# W070C.net
KiCad netlist of a schematic drawn in EAGLE
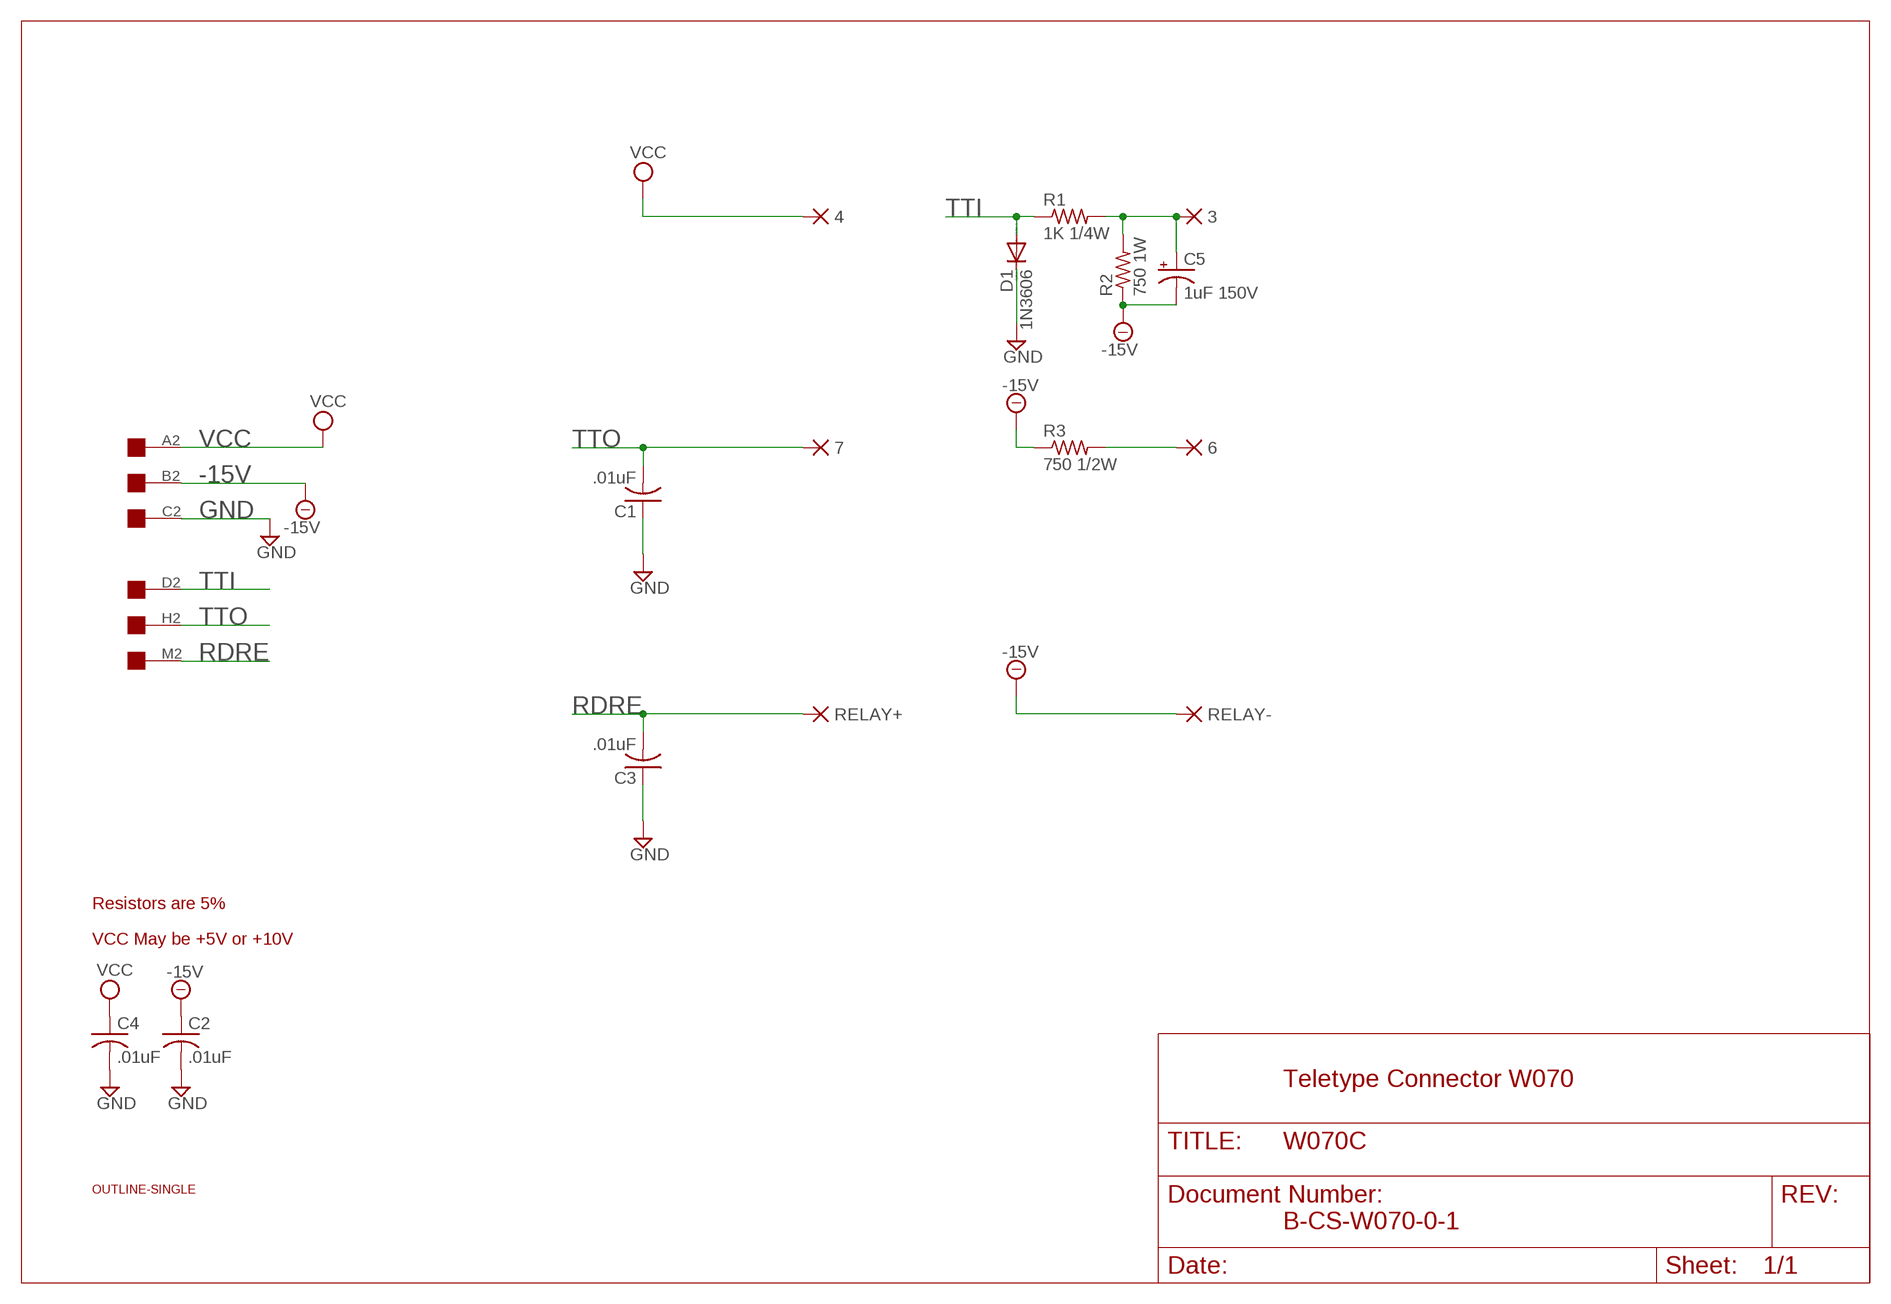
[diagram p0: schematic, sheet 1]

(export (version "E")
  (design (tool "Eeschema 10.0.6"))
  (components
    (comp (ref "3")
      (value "PAD-0465")
      (footprint "eagle-import:0465")
      (libsource (lib "eagle-import") (part "PAD-0465"))
    )
    (comp (ref "4")
      (value "PAD-0465")
      (footprint "eagle-import:0465")
      (libsource (lib "eagle-import") (part "PAD-0465"))
    )
    (comp (ref "6")
      (value "PAD-0465")
      (footprint "eagle-import:0465")
      (libsource (lib "eagle-import") (part "PAD-0465"))
    )
    (comp (ref "7")
      (value "PAD-0465")
      (footprint "eagle-import:0465")
      (libsource (lib "eagle-import") (part "PAD-0465"))
    )
    (comp (ref "C1")
      (value ".01uF")
      (footprint "eagle-import:C050-025X075")
      (libsource (lib "eagle-import") (part "C-US050-025X075"))
    )
    (comp (ref "C2")
      (value ".01uF")
      (footprint "eagle-import:C050-025X075")
      (libsource (lib "eagle-import") (part "C-US050-025X075"))
    )
    (comp (ref "C3")
      (value ".01uF")
      (footprint "eagle-import:C050-025X075")
      (libsource (lib "eagle-import") (part "C-US050-025X075"))
    )
    (comp (ref "C4")
      (value ".01uF")
      (footprint "eagle-import:C050-025X075")
      (libsource (lib "eagle-import") (part "C-US050-025X075"))
    )
    (comp (ref "C5")
      (value "1uF 150V")
      (footprint "eagle-import:E25-9")
      (libsource (lib "eagle-import") (part "CPOL-USE25-9AXIAL"))
    )
    (comp (ref "D1")
      (value "1N3606")
      (footprint "eagle-import:DO35-10")
      (libsource (lib "eagle-import") (part "1N4148DO35-10"))
    )
    (comp (ref "EDGE")
      (value "EDGE-1")
      (footprint "eagle-import:EDGE-CON1")
      (libsource (lib "eagle-import") (part "EDGE-1"))
    )
    (comp (ref "R1")
      (value "1K 1/4W")
      (footprint "eagle-import:0207_10")
      (libsource (lib "eagle-import") (part "R-US_0207/10"))
    )
    (comp (ref "R2")
      (value "750 1W")
      (footprint "eagle-import:0411_12")
      (libsource (lib "eagle-import") (part "R-US_0411/12"))
    )
    (comp (ref "R3")
      (value "750 1/2W")
      (footprint "eagle-import:0309_12")
      (libsource (lib "eagle-import") (part "R-US_0309/12"))
    )
    (comp (ref "RELAY+")
      (value "PAD-0465")
      (footprint "eagle-import:0465")
      (libsource (lib "eagle-import") (part "PAD-0465"))
    )
    (comp (ref "RELAY-")
      (value "PAD-0465")
      (footprint "eagle-import:0465")
      (libsource (lib "eagle-import") (part "PAD-0465"))
    )
    (comp (ref "U$1")
      (value "OUTLINE-SINGLE")
      (footprint "eagle-import:SINGLE")
      (libsource (lib "eagle-import") (part "OUTLINE-SINGLE"))
    )
  )
  (nets
    (net (code "1") (name "-15V") (class "Default")
      (node (ref "C2") (pin "1") (pinfunction "1_1") (pintype "passive"))
      (node (ref "C5") (pin "-") (pinfunction "-_-") (pintype "passive"))
      (node (ref "EDGE") (pin "B2") (pinfunction "1_B2") (pintype "bidirectional"))
      (node (ref "R2") (pin "1") (pinfunction "1_1") (pintype "passive"))
      (node (ref "R3") (pin "1") (pinfunction "1_1") (pintype "passive"))
      (node (ref "RELAY-") (pin "P$1") (pinfunction "P_P$1") (pintype "passive"))
    )
    (net (code "2") (name "/RDRE") (class "Default")
      (node (ref "C3") (pin "2") (pinfunction "2_2") (pintype "passive"))
      (node (ref "EDGE") (pin "M2") (pinfunction "1_M2") (pintype "bidirectional"))
      (node (ref "RELAY+") (pin "P$1") (pinfunction "P_P$1") (pintype "passive"))
    )
    (net (code "3") (name "/TTI") (class "Default")
      (node (ref "D1") (pin "A") (pinfunction "A_A") (pintype "passive"))
      (node (ref "EDGE") (pin "D2") (pinfunction "1_D2") (pintype "bidirectional"))
      (node (ref "R1") (pin "1") (pinfunction "1_1") (pintype "passive"))
    )
    (net (code "4") (name "/TTO") (class "Default")
      (node (ref "7") (pin "P$1") (pinfunction "P_P$1") (pintype "passive"))
      (node (ref "C1") (pin "2") (pinfunction "2_2") (pintype "passive"))
      (node (ref "EDGE") (pin "H2") (pinfunction "1_H2") (pintype "bidirectional"))
    )
    (net (code "5") (name "GND") (class "Default")
      (node (ref "C1") (pin "1") (pinfunction "1_1") (pintype "passive"))
      (node (ref "C2") (pin "2") (pinfunction "2_2") (pintype "passive"))
      (node (ref "C3") (pin "1") (pinfunction "1_1") (pintype "passive"))
      (node (ref "C4") (pin "2") (pinfunction "2_2") (pintype "passive"))
      (node (ref "D1") (pin "C") (pinfunction "C_C") (pintype "passive"))
      (node (ref "EDGE") (pin "C2") (pinfunction "1_C2") (pintype "bidirectional"))
    )
    (net (code "6") (name "Net-(3-P)") (class "Default")
      (node (ref "3") (pin "P$1") (pinfunction "P_P$1") (pintype "passive"))
      (node (ref "C5") (pin "+") (pinfunction "+_+") (pintype "passive"))
      (node (ref "R1") (pin "2") (pinfunction "2_2") (pintype "passive"))
      (node (ref "R2") (pin "2") (pinfunction "2_2") (pintype "passive"))
    )
    (net (code "7") (name "Net-(6-P)") (class "Default")
      (node (ref "6") (pin "P$1") (pinfunction "P_P$1") (pintype "passive"))
      (node (ref "R3") (pin "2") (pinfunction "2_2") (pintype "passive"))
    )
    (net (code "8") (name "VCC") (class "Default")
      (node (ref "4") (pin "P$1") (pinfunction "P_P$1") (pintype "passive"))
      (node (ref "C4") (pin "1") (pinfunction "1_1") (pintype "passive"))
      (node (ref "EDGE") (pin "A2") (pinfunction "1_A2") (pintype "bidirectional"))
    )
  )
)
